# MDB2USB.net
KiCad netlist of a schematic drawn in EAGLE
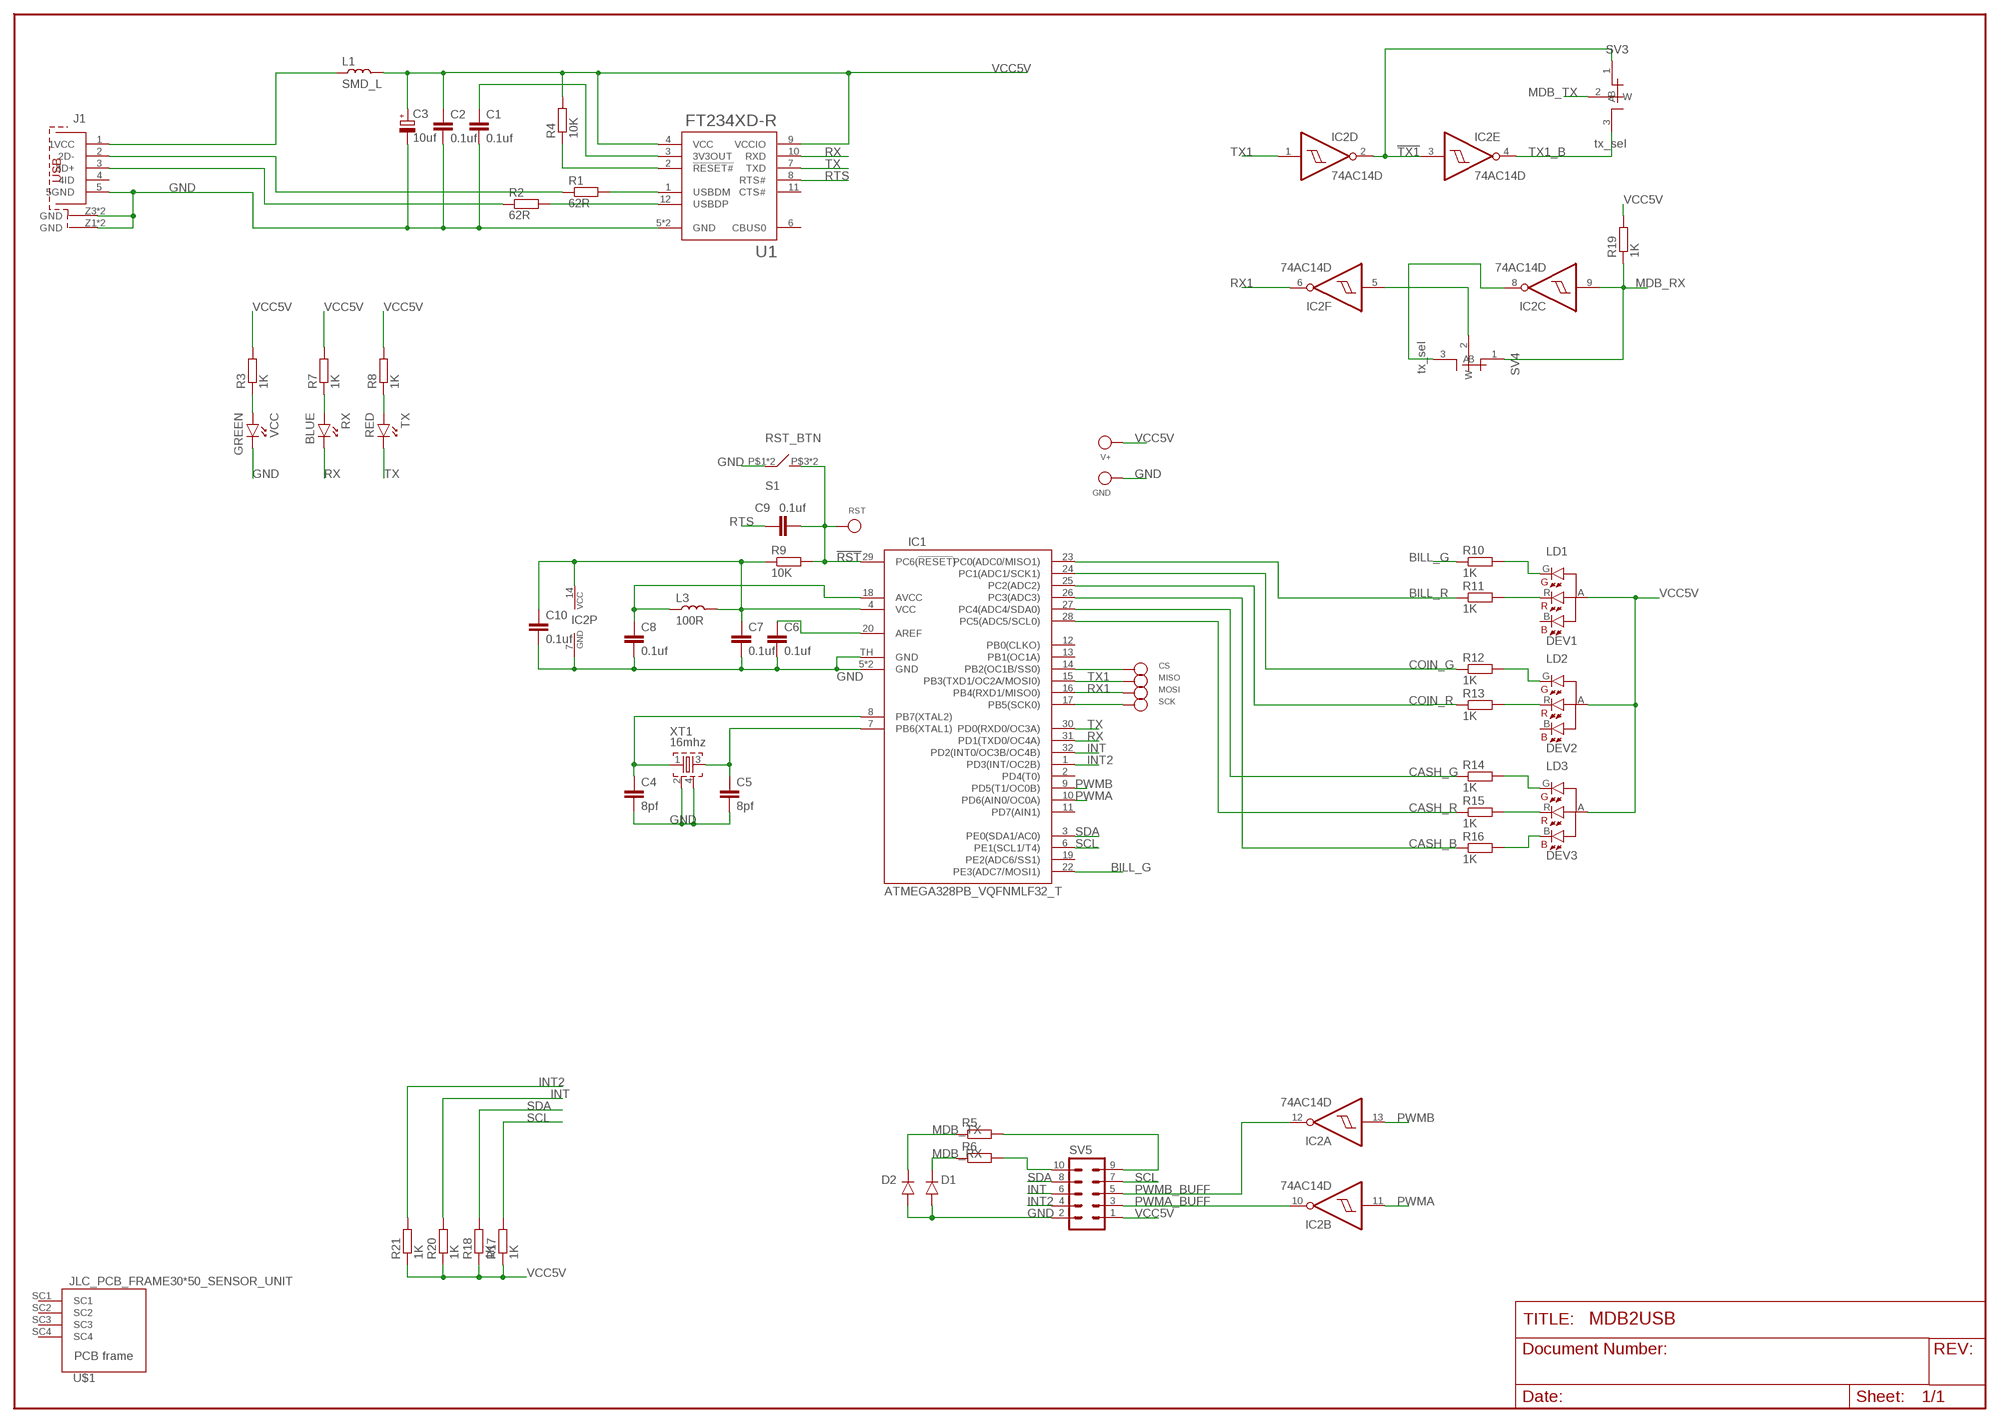
[diagram p0: schematic, sheet 1]

(export (version "E")
  (design (tool "Eeschema 10.0.6"))
  (components
    (comp (ref "C1")
      (value "0.1uf")
      (footprint "eagle-import:0603")
      (libsource (lib "eagle-import") (part "SMD_C0603"))
    )
    (comp (ref "C2")
      (value "0.1uf")
      (footprint "eagle-import:0603")
      (libsource (lib "eagle-import") (part "SMD_C0603"))
    )
    (comp (ref "C3")
      (value "10uf")
      (footprint "eagle-import:KA-3528ASYC")
      (libsource (lib "eagle-import") (part "TANTAL_150UF_3528"))
    )
    (comp (ref "C4")
      (value "8pf")
      (footprint "eagle-import:0603")
      (libsource (lib "eagle-import") (part "SMD_C0603"))
    )
    (comp (ref "C5")
      (value "8pf")
      (footprint "eagle-import:0603")
      (libsource (lib "eagle-import") (part "SMD_C0603"))
    )
    (comp (ref "C6")
      (value "0.1uf")
      (footprint "eagle-import:0603")
      (libsource (lib "eagle-import") (part "SMD_C0603"))
    )
    (comp (ref "C7")
      (value "0.1uf")
      (footprint "eagle-import:0603")
      (libsource (lib "eagle-import") (part "SMD_C0603"))
    )
    (comp (ref "C8")
      (value "0.1uf")
      (footprint "eagle-import:0603")
      (libsource (lib "eagle-import") (part "SMD_C0603"))
    )
    (comp (ref "C9")
      (value "0.1uf")
      (footprint "eagle-import:0603")
      (libsource (lib "eagle-import") (part "SMD_C0603"))
    )
    (comp (ref "C10")
      (value "0.1uf")
      (footprint "eagle-import:0603")
      (libsource (lib "eagle-import") (part "SMD_C0603"))
    )
    (comp (ref "CS")
      (value "TEST_POINT_D2MM")
      (footprint "eagle-import:TP")
      (libsource (lib "eagle-import") (part "TEST_POINT_D2MM"))
    )
    (comp (ref "D1")
      (value "D_MBRA340G")
      (footprint "eagle-import:SMA403D")
      (libsource (lib "eagle-import") (part "D_MBRA340G"))
    )
    (comp (ref "D2")
      (value "D_MBRA340G")
      (footprint "eagle-import:SMA403D")
      (libsource (lib "eagle-import") (part "D_MBRA340G"))
    )
    (comp (ref "GND")
      (value "TEST_POINT_D2MM")
      (footprint "eagle-import:TP")
      (libsource (lib "eagle-import") (part "TEST_POINT_D2MM"))
    )
    (comp (ref "IC1")
      (value "ATMEGA328PB_VQFNMLF32_T")
      (footprint "eagle-import:MLF32-TH")
      (libsource (lib "eagle-import") (part "ATMEGA328PB_VQFNMLF32_T"))
    )
    (comp (ref "IC2")
      (value "74AC14D")
      (footprint "eagle-import:SO14")
      (libsource (lib "eagle-import") (part "7414DAC"))
    )
    (comp (ref "J1")
      (value "MINI_USB_TYP_B_@")
      (footprint "eagle-import:65100516121")
      (libsource (lib "eagle-import") (part "MINI_USB_TYP_B_@"))
    )
    (comp (ref "L1")
      (value "SMD_L")
      (footprint "eagle-import:0805")
      (libsource (lib "eagle-import") (part "SMD_L"))
    )
    (comp (ref "L3")
      (value "100R")
      (footprint "eagle-import:0603")
      (libsource (lib "eagle-import") (part "SMD_L0603"))
    )
    (comp (ref "LD1")
      (value "DEV1")
      (footprint "eagle-import:LTSN-N213EGBW")
      (libsource (lib "eagle-import") (part "LTSN-N213EGBW(RGB_LED)"))
    )
    (comp (ref "LD2")
      (value "DEV2")
      (footprint "eagle-import:LTSN-N213EGBW")
      (libsource (lib "eagle-import") (part "LTSN-N213EGBW(RGB_LED)"))
    )
    (comp (ref "LD3")
      (value "DEV3")
      (footprint "eagle-import:LTSN-N213EGBW")
      (libsource (lib "eagle-import") (part "LTSN-N213EGBW(RGB_LED)"))
    )
    (comp (ref "MISO")
      (value "TEST_POINT_D2MM")
      (footprint "eagle-import:TP")
      (libsource (lib "eagle-import") (part "TEST_POINT_D2MM"))
    )
    (comp (ref "MOSI")
      (value "TEST_POINT_D2MM")
      (footprint "eagle-import:TP")
      (libsource (lib "eagle-import") (part "TEST_POINT_D2MM"))
    )
    (comp (ref "R1")
      (value "62R")
      (footprint "eagle-import:0603")
      (libsource (lib "eagle-import") (part "SMD_R0603"))
    )
    (comp (ref "R2")
      (value "62R")
      (footprint "eagle-import:0603")
      (libsource (lib "eagle-import") (part "SMD_R0603"))
    )
    (comp (ref "R3")
      (value "1K")
      (footprint "eagle-import:0603")
      (libsource (lib "eagle-import") (part "SMD_R0603"))
    )
    (comp (ref "R4")
      (value "10K")
      (footprint "eagle-import:0603")
      (libsource (lib "eagle-import") (part "SMD_R0603"))
    )
    (comp (ref "R5")
      (value "SMD_R1206")
      (footprint "eagle-import:1206")
      (libsource (lib "eagle-import") (part "SMD_R1206"))
    )
    (comp (ref "R6")
      (value "SMD_R1206")
      (footprint "eagle-import:1206")
      (libsource (lib "eagle-import") (part "SMD_R1206"))
    )
    (comp (ref "R7")
      (value "1K")
      (footprint "eagle-import:0603")
      (libsource (lib "eagle-import") (part "SMD_R0603"))
    )
    (comp (ref "R8")
      (value "1K")
      (footprint "eagle-import:0603")
      (libsource (lib "eagle-import") (part "SMD_R0603"))
    )
    (comp (ref "R9")
      (value "10K")
      (footprint "eagle-import:0603")
      (libsource (lib "eagle-import") (part "SMD_R0603"))
    )
    (comp (ref "R10")
      (value "1K")
      (footprint "eagle-import:0603")
      (libsource (lib "eagle-import") (part "SMD_R0603"))
    )
    (comp (ref "R11")
      (value "1K")
      (footprint "eagle-import:0603")
      (libsource (lib "eagle-import") (part "SMD_R0603"))
    )
    (comp (ref "R12")
      (value "1K")
      (footprint "eagle-import:0603")
      (libsource (lib "eagle-import") (part "SMD_R0603"))
    )
    (comp (ref "R13")
      (value "1K")
      (footprint "eagle-import:0603")
      (libsource (lib "eagle-import") (part "SMD_R0603"))
    )
    (comp (ref "R14")
      (value "1K")
      (footprint "eagle-import:0603")
      (libsource (lib "eagle-import") (part "SMD_R0603"))
    )
    (comp (ref "R15")
      (value "1K")
      (footprint "eagle-import:0603")
      (libsource (lib "eagle-import") (part "SMD_R0603"))
    )
    (comp (ref "R16")
      (value "1K")
      (footprint "eagle-import:0603")
      (libsource (lib "eagle-import") (part "SMD_R0603"))
    )
    (comp (ref "R17")
      (value "1K")
      (footprint "eagle-import:0603")
      (libsource (lib "eagle-import") (part "SMD_R0603"))
    )
    (comp (ref "R18")
      (value "1K")
      (footprint "eagle-import:0603")
      (libsource (lib "eagle-import") (part "SMD_R0603"))
    )
    (comp (ref "R19")
      (value "1K")
      (footprint "eagle-import:0603")
      (libsource (lib "eagle-import") (part "SMD_R0603"))
    )
    (comp (ref "R20")
      (value "1K")
      (footprint "eagle-import:0603")
      (libsource (lib "eagle-import") (part "SMD_R0603"))
    )
    (comp (ref "R21")
      (value "1K")
      (footprint "eagle-import:0603")
      (libsource (lib "eagle-import") (part "SMD_R0603"))
    )
    (comp (ref "RST")
      (value "TEST_POINT_D2MM")
      (footprint "eagle-import:TP")
      (libsource (lib "eagle-import") (part "TEST_POINT_D2MM"))
    )
    (comp (ref "RX")
      (value "BLUE")
      (footprint "eagle-import:0603_P")
      (libsource (lib "eagle-import") (part "LED0603"))
    )
    (comp (ref "S1")
      (value "RST_BTN")
      (footprint "eagle-import:GALILEO_VERT_BTN")
      (libsource (lib "eagle-import") (part "GALILEO_BTN"))
    )
    (comp (ref "SCK")
      (value "TEST_POINT_D2MM")
      (footprint "eagle-import:TP")
      (libsource (lib "eagle-import") (part "TEST_POINT_D2MM"))
    )
    (comp (ref "SV3")
      (value "tx_sel")
      (footprint "eagle-import:0603_JUMP")
      (libsource (lib "eagle-import") (part "SMD_SWITCH_JUMPER"))
    )
    (comp (ref "SV4")
      (value "tx_sel")
      (footprint "eagle-import:0603_JUMP")
      (libsource (lib "eagle-import") (part "SMD_SWITCH_JUMPER"))
    )
    (comp (ref "SV5")
      (value "MA05-2")
      (footprint "eagle-import:MA05-2")
      (libsource (lib "eagle-import") (part "MA05-2"))
    )
    (comp (ref "TX")
      (value "RED")
      (footprint "eagle-import:0603_P")
      (libsource (lib "eagle-import") (part "LED0603"))
    )
    (comp (ref "U$1")
      (value "JLC_PCB_FRAME30*50_SENSOR_UNIT")
      (footprint "eagle-import:30X50_SENSOR_UNIT")
      (libsource (lib "eagle-import") (part "JLC_PCB_FRAME3050_SENSOR_UNIT"))
    )
    (comp (ref "U1")
      (value "FT234XD-R")
      (footprint "eagle-import:IC_FT234XD-R")
      (fields (field (name "MF") "FTDI,"))
      (libsource (lib "eagle-import") (part "FT234XD-R"))
    )
    (comp (ref "V+")
      (value "TEST_POINT_D2MM")
      (footprint "eagle-import:TP")
      (libsource (lib "eagle-import") (part "TEST_POINT_D2MM"))
    )
    (comp (ref "VCC")
      (value "GREEN")
      (footprint "eagle-import:0603_P")
      (libsource (lib "eagle-import") (part "LED0603"))
    )
    (comp (ref "XT1")
      (value "16mhz")
      (footprint "eagle-import:QUARTZ_3X3MM")
      (libsource (lib "eagle-import") (part "QUARTZ_ZQ"))
    )
  )
  (nets
    (net (code "1") (name "/BILL_G") (class "Default")
      (node (ref "IC1") (pin "22") (pinfunction "PE3(ADC7/MOSI1)_22") (pintype "bidirectional"))
      (node (ref "R10") (pin "1") (pinfunction "1_1") (pintype "passive"))
    )
    (net (code "2") (name "/BILL_R") (class "Default")
      (node (ref "IC1") (pin "23") (pinfunction "PC0(ADC0/MISO1)_23") (pintype "bidirectional"))
      (node (ref "R11") (pin "1") (pinfunction "1_1") (pintype "passive"))
    )
    (net (code "3") (name "/CASH_B") (class "Default")
      (node (ref "IC1") (pin "26") (pinfunction "PC3(ADC3)_26") (pintype "bidirectional"))
      (node (ref "R16") (pin "1") (pinfunction "1_1") (pintype "passive"))
    )
    (net (code "4") (name "/CASH_G") (class "Default")
      (node (ref "IC1") (pin "27") (pinfunction "PC4(ADC4/SDA0)_27") (pintype "bidirectional"))
      (node (ref "R14") (pin "1") (pinfunction "1_1") (pintype "passive"))
    )
    (net (code "5") (name "/CASH_R") (class "Default")
      (node (ref "IC1") (pin "28") (pinfunction "PC5(ADC5/SCL0)_28") (pintype "bidirectional"))
      (node (ref "R15") (pin "1") (pinfunction "1_1") (pintype "passive"))
    )
    (net (code "6") (name "/COIN_G") (class "Default")
      (node (ref "IC1") (pin "24") (pinfunction "PC1(ADC1/SCK1)_24") (pintype "bidirectional"))
      (node (ref "R12") (pin "1") (pinfunction "1_1") (pintype "passive"))
    )
    (net (code "7") (name "/COIN_R") (class "Default")
      (node (ref "IC1") (pin "25") (pinfunction "PC2(ADC2)_25") (pintype "bidirectional"))
      (node (ref "R13") (pin "1") (pinfunction "1_1") (pintype "passive"))
    )
    (net (code "8") (name "/GND") (class "Default")
      (node (ref "C1") (pin "2") (pinfunction "2_2") (pintype "passive"))
      (node (ref "C10") (pin "2") (pinfunction "2_2") (pintype "passive"))
      (node (ref "C2") (pin "2") (pinfunction "2_2") (pintype "passive"))
      (node (ref "C3") (pin "M") (pinfunction "-_M") (pintype "passive"))
      (node (ref "C4") (pin "2") (pinfunction "2_2") (pintype "passive"))
      (node (ref "C5") (pin "2") (pinfunction "2_2") (pintype "passive"))
      (node (ref "C6") (pin "2") (pinfunction "2_2") (pintype "passive"))
      (node (ref "C7") (pin "2") (pinfunction "2_2") (pintype "passive"))
      (node (ref "C8") (pin "2") (pinfunction "2_2") (pintype "passive"))
      (node (ref "D1") (pin "P$2") (pinfunction "A_P$2") (pintype "bidirectional"))
      (node (ref "D2") (pin "P$2") (pinfunction "A_P$2") (pintype "bidirectional"))
      (node (ref "GND") (pin "P$1") (pinfunction "1_P$1") (pintype "bidirectional"))
      (node (ref "IC1") (pin "21") (pinfunction "GND_21") (pintype "power_in"))
      (node (ref "IC1") (pin "5") (pinfunction "GND_5") (pintype "power_in"))
      (node (ref "IC1") (pin "TH") (pinfunction "GND_TH") (pintype "power_in"))
      (node (ref "IC2") (pin "7") (pinfunction "GND_7") (pintype "power_in"))
      (node (ref "J1") (pin "5") (pinfunction "5GND_5") (pintype "passive"))
      (node (ref "J1") (pin "Z1") (pinfunction "GND_Z1") (pintype "bidirectional"))
      (node (ref "J1") (pin "Z2") (pinfunction "GND_Z2") (pintype "bidirectional"))
      (node (ref "J1") (pin "Z3") (pinfunction "GND_Z3") (pintype "bidirectional"))
      (node (ref "J1") (pin "Z4") (pinfunction "GND_Z4") (pintype "bidirectional"))
      (node (ref "S1") (pin "P$1") (pinfunction "1_P$1") (pintype "bidirectional"))
      (node (ref "S1") (pin "P$2") (pinfunction "1_P$2") (pintype "bidirectional"))
      (node (ref "SV5") (pin "2") (pinfunction "2_2") (pintype "passive"))
      (node (ref "U1") (pin "13") (pinfunction "GND_13") (pintype "power_in"))
      (node (ref "U1") (pin "5") (pinfunction "GND_5") (pintype "power_in"))
      (node (ref "VCC") (pin "1") (pinfunction "K_1") (pintype "bidirectional"))
      (node (ref "XT1") (pin "2") (pinfunction "2_2") (pintype "passive"))
      (node (ref "XT1") (pin "4") (pinfunction "4_4") (pintype "passive"))
    )
    (net (code "9") (name "/INT") (class "Default")
      (node (ref "IC1") (pin "32") (pinfunction "PD2(INT0/OC3B/OC4B)_32") (pintype "bidirectional"))
      (node (ref "R20") (pin "2") (pinfunction "2_2") (pintype "passive"))
      (node (ref "SV5") (pin "6") (pinfunction "6_6") (pintype "passive"))
    )
    (net (code "10") (name "/INT2") (class "Default")
      (node (ref "IC1") (pin "1") (pinfunction "PD3(INT/OC2B)_1") (pintype "bidirectional"))
      (node (ref "R21") (pin "2") (pinfunction "2_2") (pintype "passive"))
      (node (ref "SV5") (pin "4") (pinfunction "4_4") (pintype "passive"))
    )
    (net (code "11") (name "/MDB_RX") (class "Default")
      (node (ref "D2") (pin "P$1") (pinfunction "C_P$1") (pintype "bidirectional"))
      (node (ref "IC2") (pin "9") (pinfunction "I_9") (pintype "input"))
      (node (ref "R19") (pin "1") (pinfunction "1_1") (pintype "passive"))
      (node (ref "R6") (pin "1") (pinfunction "1_1") (pintype "passive"))
      (node (ref "SV4") (pin "1") (pinfunction "A_1") (pintype "bidirectional"))
    )
    (net (code "12") (name "/MDB_TX") (class "Default")
      (node (ref "D1") (pin "P$1") (pinfunction "C_P$1") (pintype "bidirectional"))
      (node (ref "R5") (pin "1") (pinfunction "1_1") (pintype "passive"))
      (node (ref "SV3") (pin "2") (pinfunction "W_2") (pintype "bidirectional"))
    )
    (net (code "13") (name "/PWMA") (class "Default")
      (node (ref "IC1") (pin "10") (pinfunction "PD6(AIN0/OC0A)_10") (pintype "bidirectional"))
      (node (ref "IC2") (pin "11") (pinfunction "I_11") (pintype "input"))
    )
    (net (code "14") (name "/PWMA_BUFF") (class "Default")
      (node (ref "IC2") (pin "10") (pinfunction "O_10") (pintype "output"))
      (node (ref "SV5") (pin "3") (pinfunction "3_3") (pintype "passive"))
    )
    (net (code "15") (name "/PWMB") (class "Default")
      (node (ref "IC1") (pin "9") (pinfunction "PD5(T1/OC0B)_9") (pintype "bidirectional"))
      (node (ref "IC2") (pin "13") (pinfunction "I_13") (pintype "input"))
    )
    (net (code "16") (name "/PWMB_BUFF") (class "Default")
      (node (ref "IC2") (pin "12") (pinfunction "O_12") (pintype "output"))
      (node (ref "SV5") (pin "5") (pinfunction "5_5") (pintype "passive"))
    )
    (net (code "17") (name "/RTS") (class "Default")
      (node (ref "C9") (pin "1") (pinfunction "1_1") (pintype "passive"))
      (node (ref "U1") (pin "8") (pinfunction "RTS#_8") (pintype "output"))
    )
    (net (code "18") (name "/RX") (class "Default")
      (node (ref "IC1") (pin "31") (pinfunction "PD1(TXD0/OC4A)_31") (pintype "bidirectional"))
      (node (ref "RX") (pin "1") (pinfunction "K_1") (pintype "bidirectional"))
      (node (ref "U1") (pin "10") (pinfunction "RXD_10") (pintype "input"))
    )
    (net (code "19") (name "/RX1") (class "Default")
      (node (ref "IC1") (pin "16") (pinfunction "PB4(RXD1/MISO0)_16") (pintype "bidirectional"))
      (node (ref "IC2") (pin "6") (pinfunction "O_6") (pintype "output"))
      (node (ref "MOSI") (pin "P$1") (pinfunction "1_P$1") (pintype "bidirectional"))
    )
    (net (code "20") (name "/SCL") (class "Default")
      (node (ref "IC1") (pin "6") (pinfunction "PE1(SCL1/T4)_6") (pintype "bidirectional"))
      (node (ref "R17") (pin "2") (pinfunction "2_2") (pintype "passive"))
      (node (ref "SV5") (pin "7") (pinfunction "7_7") (pintype "passive"))
    )
    (net (code "21") (name "/SDA") (class "Default")
      (node (ref "IC1") (pin "3") (pinfunction "PE0(SDA1/AC0)_3") (pintype "bidirectional"))
      (node (ref "R18") (pin "2") (pinfunction "2_2") (pintype "passive"))
      (node (ref "SV5") (pin "8") (pinfunction "8_8") (pintype "passive"))
    )
    (net (code "22") (name "/TX") (class "Default")
      (node (ref "IC1") (pin "30") (pinfunction "PD0(RXD0/OC3A)_30") (pintype "bidirectional"))
      (node (ref "TX") (pin "1") (pinfunction "K_1") (pintype "bidirectional"))
      (node (ref "U1") (pin "7") (pinfunction "TXD_7") (pintype "output"))
    )
    (net (code "23") (name "/TX1") (class "Default")
      (node (ref "IC1") (pin "15") (pinfunction "PB3(TXD1/OC2A/MOSI0)_15") (pintype "bidirectional"))
      (node (ref "IC2") (pin "1") (pinfunction "I_1") (pintype "input"))
      (node (ref "MISO") (pin "P$1") (pinfunction "1_P$1") (pintype "bidirectional"))
    )
    (net (code "24") (name "/TX1_B") (class "Default")
      (node (ref "IC2") (pin "4") (pinfunction "O_4") (pintype "output"))
      (node (ref "SV3") (pin "3") (pinfunction "B_3") (pintype "bidirectional"))
    )
    (net (code "25") (name "/VCC5V") (class "Default")
      (node (ref "C10") (pin "1") (pinfunction "1_1") (pintype "passive"))
      (node (ref "C2") (pin "1") (pinfunction "1_1") (pintype "passive"))
      (node (ref "C3") (pin "P") (pinfunction "+_P") (pintype "passive"))
      (node (ref "C7") (pin "1") (pinfunction "1_1") (pintype "passive"))
      (node (ref "IC1") (pin "4") (pinfunction "VCC_4") (pintype "power_in"))
      (node (ref "IC2") (pin "14") (pinfunction "VCC_14") (pintype "power_in"))
      (node (ref "L1") (pin "2") (pinfunction "2_2") (pintype "passive"))
      (node (ref "L3") (pin "2") (pinfunction "2_2") (pintype "passive"))
      (node (ref "LD1") (pin "A") (pinfunction "A_A") (pintype "passive"))
      (node (ref "LD2") (pin "A") (pinfunction "A_A") (pintype "passive"))
      (node (ref "LD3") (pin "A") (pinfunction "A_A") (pintype "passive"))
      (node (ref "R17") (pin "1") (pinfunction "1_1") (pintype "passive"))
      (node (ref "R18") (pin "1") (pinfunction "1_1") (pintype "passive"))
      (node (ref "R19") (pin "2") (pinfunction "2_2") (pintype "passive"))
      (node (ref "R20") (pin "1") (pinfunction "1_1") (pintype "passive"))
      (node (ref "R21") (pin "1") (pinfunction "1_1") (pintype "passive"))
      (node (ref "R3") (pin "2") (pinfunction "2_2") (pintype "passive"))
      (node (ref "R4") (pin "2") (pinfunction "2_2") (pintype "passive"))
      (node (ref "R7") (pin "2") (pinfunction "2_2") (pintype "passive"))
      (node (ref "R8") (pin "2") (pinfunction "2_2") (pintype "passive"))
      (node (ref "R9") (pin "1") (pinfunction "1_1") (pintype "passive"))
      (node (ref "SV5") (pin "1") (pinfunction "1_1") (pintype "passive"))
      (node (ref "U1") (pin "4") (pinfunction "VCC_4") (pintype "power_in"))
      (node (ref "U1") (pin "9") (pinfunction "VCCIO_9") (pintype "power_in"))
      (node (ref "V+") (pin "P$1") (pinfunction "1_P$1") (pintype "bidirectional"))
    )
    (net (code "26") (name "/~{RST}") (class "Default")
      (node (ref "C9") (pin "2") (pinfunction "2_2") (pintype "passive"))
      (node (ref "IC1") (pin "29") (pinfunction "PC6(~{RESET})_29") (pintype "bidirectional"))
      (node (ref "R9") (pin "2") (pinfunction "2_2") (pintype "passive"))
      (node (ref "RST") (pin "P$1") (pinfunction "1_P$1") (pintype "bidirectional"))
      (node (ref "S1") (pin "P$3") (pinfunction "4_P$3") (pintype "bidirectional"))
      (node (ref "S1") (pin "P$4") (pinfunction "4_P$4") (pintype "bidirectional"))
    )
    (net (code "27") (name "/~{TX1}") (class "Default")
      (node (ref "IC2") (pin "2") (pinfunction "O_2") (pintype "output"))
      (node (ref "IC2") (pin "3") (pinfunction "I_3") (pintype "input"))
      (node (ref "SV3") (pin "1") (pinfunction "A_1") (pintype "bidirectional"))
    )
    (net (code "28") (name "Net-(CS-1)") (class "Default")
      (node (ref "CS") (pin "P$1") (pinfunction "1_P$1") (pintype "bidirectional"))
      (node (ref "IC1") (pin "14") (pinfunction "PB2(OC1B/SS0)_14") (pintype "bidirectional"))
    )
    (net (code "29") (name "Net-(IC1-AREF)") (class "Default")
      (node (ref "C6") (pin "1") (pinfunction "1_1") (pintype "passive"))
      (node (ref "IC1") (pin "20") (pinfunction "AREF_20") (pintype "passive"))
    )
    (net (code "30") (name "Net-(IC1-AVCC)") (class "Default")
      (node (ref "C8") (pin "1") (pinfunction "1_1") (pintype "passive"))
      (node (ref "IC1") (pin "18") (pinfunction "AVCC_18") (pintype "power_in"))
      (node (ref "L3") (pin "1") (pinfunction "1_1") (pintype "passive"))
    )
    (net (code "31") (name "Net-(IC1-PB5(SCK0))") (class "Default")
      (node (ref "IC1") (pin "17") (pinfunction "PB5(SCK0)_17") (pintype "bidirectional"))
      (node (ref "SCK") (pin "P$1") (pinfunction "1_P$1") (pintype "bidirectional"))
    )
    (net (code "32") (name "Net-(IC1-PB6(XTAL1))") (class "Default")
      (node (ref "C5") (pin "1") (pinfunction "1_1") (pintype "passive"))
      (node (ref "IC1") (pin "7") (pinfunction "PB6(XTAL1)_7") (pintype "bidirectional"))
      (node (ref "XT1") (pin "3") (pinfunction "3_3") (pintype "passive"))
    )
    (net (code "33") (name "Net-(IC1-PB7(XTAL2))") (class "Default")
      (node (ref "C4") (pin "1") (pinfunction "1_1") (pintype "passive"))
      (node (ref "IC1") (pin "8") (pinfunction "PB7(XTAL2)_8") (pintype "bidirectional"))
      (node (ref "XT1") (pin "1") (pinfunction "1_1") (pintype "passive"))
    )
    (net (code "34") (name "Net-(IC2C-O)") (class "Default")
      (node (ref "IC2") (pin "8") (pinfunction "O_8") (pintype "output"))
      (node (ref "SV4") (pin "3") (pinfunction "B_3") (pintype "bidirectional"))
    )
    (net (code "35") (name "Net-(IC2F-I)") (class "Default")
      (node (ref "IC2") (pin "5") (pinfunction "I_5") (pintype "input"))
      (node (ref "SV4") (pin "2") (pinfunction "W_2") (pintype "bidirectional"))
    )
    (net (code "36") (name "Net-(J1-1VCC)") (class "Default")
      (node (ref "J1") (pin "1") (pinfunction "1VCC_1") (pintype "passive"))
      (node (ref "L1") (pin "1") (pinfunction "1_1") (pintype "passive"))
    )
    (net (code "37") (name "Net-(J1-2D-)") (class "Default")
      (node (ref "J1") (pin "2") (pinfunction "2D-_2") (pintype "passive"))
      (node (ref "R1") (pin "1") (pinfunction "1_1") (pintype "passive"))
    )
    (net (code "38") (name "Net-(J1-3D+)") (class "Default")
      (node (ref "J1") (pin "3") (pinfunction "3D+_3") (pintype "passive"))
      (node (ref "R2") (pin "1") (pinfunction "1_1") (pintype "passive"))
    )
    (net (code "39") (name "Net-(LD1-GC)") (class "Default")
      (node (ref "LD1") (pin "G") (pinfunction "GC_G") (pintype "passive"))
      (node (ref "R10") (pin "2") (pinfunction "2_2") (pintype "passive"))
    )
    (net (code "40") (name "Net-(LD1-RC)") (class "Default")
      (node (ref "LD1") (pin "R") (pinfunction "RC_R") (pintype "passive"))
      (node (ref "R11") (pin "2") (pinfunction "2_2") (pintype "passive"))
    )
    (net (code "41") (name "Net-(LD2-GC)") (class "Default")
      (node (ref "LD2") (pin "G") (pinfunction "GC_G") (pintype "passive"))
      (node (ref "R12") (pin "2") (pinfunction "2_2") (pintype "passive"))
    )
    (net (code "42") (name "Net-(LD2-RC)") (class "Default")
      (node (ref "LD2") (pin "R") (pinfunction "RC_R") (pintype "passive"))
      (node (ref "R13") (pin "2") (pinfunction "2_2") (pintype "passive"))
    )
    (net (code "43") (name "Net-(LD3-BC)") (class "Default")
      (node (ref "LD3") (pin "B") (pinfunction "BC_B") (pintype "passive"))
      (node (ref "R16") (pin "2") (pinfunction "2_2") (pintype "passive"))
    )
    (net (code "44") (name "Net-(LD3-GC)") (class "Default")
      (node (ref "LD3") (pin "G") (pinfunction "GC_G") (pintype "passive"))
      (node (ref "R14") (pin "2") (pinfunction "2_2") (pintype "passive"))
    )
    (net (code "45") (name "Net-(LD3-RC)") (class "Default")
      (node (ref "LD3") (pin "R") (pinfunction "RC_R") (pintype "passive"))
      (node (ref "R15") (pin "2") (pinfunction "2_2") (pintype "passive"))
    )
    (net (code "46") (name "Net-(R5-Pad2)") (class "Default")
      (node (ref "R5") (pin "2") (pinfunction "2_2") (pintype "passive"))
      (node (ref "SV5") (pin "9") (pinfunction "9_9") (pintype "passive"))
    )
    (net (code "47") (name "Net-(R6-Pad2)") (class "Default")
      (node (ref "R6") (pin "2") (pinfunction "2_2") (pintype "passive"))
      (node (ref "SV5") (pin "10") (pinfunction "10_10") (pintype "passive"))
    )
    (net (code "48") (name "Net-(RX-A)") (class "Default")
      (node (ref "R7") (pin "1") (pinfunction "1_1") (pintype "passive"))
      (node (ref "RX") (pin "2") (pinfunction "A_2") (pintype "bidirectional"))
    )
    (net (code "49") (name "Net-(TX-A)") (class "Default")
      (node (ref "R8") (pin "1") (pinfunction "1_1") (pintype "passive"))
      (node (ref "TX") (pin "2") (pinfunction "A_2") (pintype "bidirectional"))
    )
    (net (code "50") (name "Net-(U1-3V3OUT)") (class "Default")
      (node (ref "C1") (pin "1") (pinfunction "1_1") (pintype "passive"))
      (node (ref "U1") (pin "3") (pinfunction "3V3OUT_3") (pintype "output"))
    )
    (net (code "51") (name "Net-(U1-USBDM)") (class "Default")
      (node (ref "R1") (pin "2") (pinfunction "2_2") (pintype "passive"))
      (node (ref "U1") (pin "1") (pinfunction "USBDM_1") (pintype "bidirectional"))
    )
    (net (code "52") (name "Net-(U1-USBDP)") (class "Default")
      (node (ref "R2") (pin "2") (pinfunction "2_2") (pintype "passive"))
      (node (ref "U1") (pin "12") (pinfunction "USBDP_12") (pintype "bidirectional"))
    )
    (net (code "53") (name "Net-(U1-~{RESET#})") (class "Default")
      (node (ref "R4") (pin "1") (pinfunction "1_1") (pintype "passive"))
      (node (ref "U1") (pin "2") (pinfunction "~{RESET#}_2") (pintype "input"))
    )
    (net (code "54") (name "Net-(VCC-A)") (class "Default")
      (node (ref "R3") (pin "1") (pinfunction "1_1") (pintype "passive"))
      (node (ref "VCC") (pin "2") (pinfunction "A_2") (pintype "bidirectional"))
    )
    (net (code "55") (name "unconnected-(IC1-PB0(CLKO)-Pad12)") (class "Default")
      (node (ref "IC1") (pin "12") (pinfunction "PB0(CLKO)_12") (pintype "bidirectional"))
    )
    (net (code "56") (name "unconnected-(IC1-PB1(OC1A)-Pad13)") (class "Default")
      (node (ref "IC1") (pin "13") (pinfunction "PB1(OC1A)_13") (pintype "bidirectional"))
    )
    (net (code "57") (name "unconnected-(IC1-PD4(T0)-Pad2)") (class "Default")
      (node (ref "IC1") (pin "2") (pinfunction "PD4(T0)_2") (pintype "bidirectional"))
    )
    (net (code "58") (name "unconnected-(IC1-PD7(AIN1)-Pad11)") (class "Default")
      (node (ref "IC1") (pin "11") (pinfunction "PD7(AIN1)_11") (pintype "bidirectional"))
    )
    (net (code "59") (name "unconnected-(IC1-PE2(ADC6{slash}SS1)-Pad19)") (class "Default")
      (node (ref "IC1") (pin "19") (pinfunction "PE2(ADC6/SS1)_19") (pintype "bidirectional"))
    )
    (net (code "60") (name "unconnected-(J1-4ID-Pad4)") (class "Default")
      (node (ref "J1") (pin "4") (pinfunction "4ID_4") (pintype "passive"))
    )
    (net (code "61") (name "unconnected-(LD1-BC-PadB)") (class "Default")
      (node (ref "LD1") (pin "B") (pinfunction "BC_B") (pintype "passive"))
    )
    (net (code "62") (name "unconnected-(LD2-BC-PadB)") (class "Default")
      (node (ref "LD2") (pin "B") (pinfunction "BC_B") (pintype "passive"))
    )
    (net (code "63") (name "unconnected-(U$1-PadSC1)") (class "Default")
      (node (ref "U$1") (pin "SC1") (pinfunction "SC1_SC1") (pintype "bidirectional"))
    )
    (net (code "64") (name "unconnected-(U$1-PadSC2)") (class "Default")
      (node (ref "U$1") (pin "SC2") (pinfunction "SC2_SC2") (pintype "bidirectional"))
    )
    (net (code "65") (name "unconnected-(U$1-PadSC3)") (class "Default")
      (node (ref "U$1") (pin "SC3") (pinfunction "SC3_SC3") (pintype "bidirectional"))
    )
    (net (code "66") (name "unconnected-(U$1-PadSC4)") (class "Default")
      (node (ref "U$1") (pin "SC4") (pinfunction "SC4_SC4") (pintype "bidirectional"))
    )
    (net (code "67") (name "unconnected-(U1-CBUS0-Pad6)") (class "Default")
      (node (ref "U1") (pin "6") (pinfunction "CBUS0_6") (pintype "bidirectional"))
    )
    (net (code "68") (name "unconnected-(U1-CTS#-Pad11)") (class "Default")
      (node (ref "U1") (pin "11") (pinfunction "CTS#_11") (pintype "input"))
    )
  )
)
